# LCD_Disp_AIR.net
KiCad netlist of a schematic drawn in EAGLE
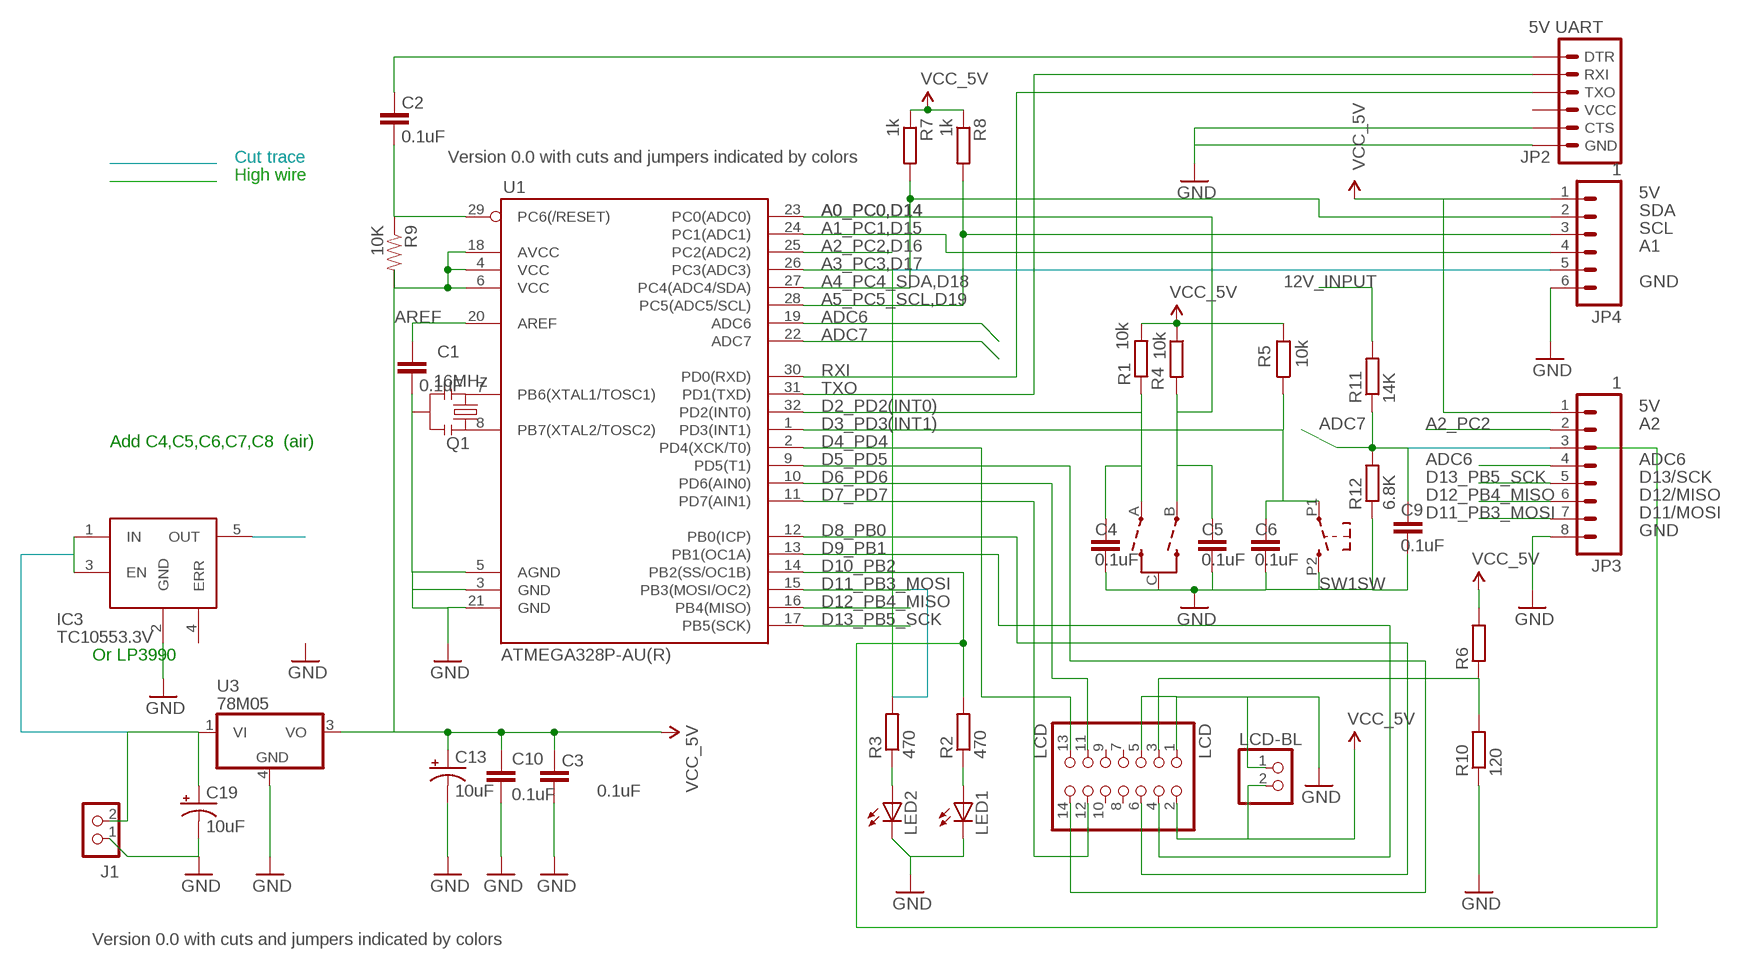
[diagram p0: schematic, sheet 1]

(export (version "E")
  (design (tool "Eeschema 10.0.6"))
  (components
    (comp (ref "C1")
      (value "0.1uF")
      (footprint "eagle-import:0805")
      (libsource (lib "eagle-import") (part "CAP0805"))
    )
    (comp (ref "C2")
      (value "0.1uF")
      (footprint "eagle-import:0805")
      (libsource (lib "eagle-import") (part "CAP0805"))
    )
    (comp (ref "C3")
      (value "0.1uF")
      (footprint "eagle-import:0805")
      (libsource (lib "eagle-import") (part "CAP0805"))
    )
    (comp (ref "C4")
      (value "0.1uF")
      (footprint "eagle-import:0805")
      (libsource (lib "eagle-import") (part "CAP0805"))
    )
    (comp (ref "C5")
      (value "0.1uF")
      (footprint "eagle-import:0805")
      (libsource (lib "eagle-import") (part "CAP0805"))
    )
    (comp (ref "C6")
      (value "0.1uF")
      (footprint "eagle-import:0805")
      (libsource (lib "eagle-import") (part "CAP0805"))
    )
    (comp (ref "C9")
      (value "0.1uF")
      (footprint "eagle-import:0805")
      (libsource (lib "eagle-import") (part "CAP0805"))
    )
    (comp (ref "C10")
      (value "0.1uF")
      (footprint "eagle-import:0805")
      (libsource (lib "eagle-import") (part "CAP0805"))
    )
    (comp (ref "C13")
      (value "10uF")
      (footprint "eagle-import:EIA3216")
      (libsource (lib "eagle-import") (part "CAP_POL1206"))
    )
    (comp (ref "C19")
      (value "10uF")
      (footprint "eagle-import:EIA7343")
      (libsource (lib "eagle-import") (part "CAP_POL7343"))
    )
    (comp (ref "IC3")
      (value "TC10553.3V")
      (footprint "eagle-import:SOT23-5")
      (libsource (lib "eagle-import") (part "TC10553.3V"))
    )
    (comp (ref "J1")
      (value "12V input")
      (footprint "eagle-import:M1X2")
      (libsource (lib "eagle-import") (part "CON_HEADER_1X02-PTH"))
    )
    (comp (ref "JP2")
      (value "5V UART")
      (footprint "eagle-import:1X06")
      (libsource (lib "eagle-import") (part "ARDUINO_SERIAL_PROGRAMPTH"))
    )
    (comp (ref "JP3")
      (value "1")
      (footprint "eagle-import:1X08")
      (libsource (lib "eagle-import") (part "M081X08"))
    )
    (comp (ref "JP4")
      (value "1")
      (footprint "eagle-import:1X06")
      (libsource (lib "eagle-import") (part "M06SIP"))
    )
    (comp (ref "LCD")
      (value "LCD")
      (footprint "eagle-import:2X07")
      (libsource (lib "eagle-import") (part "PINHD-2X7"))
    )
    (comp (ref "LCD-BL")
      (value "PINHD-1X2")
      (footprint "eagle-import:1X02")
      (libsource (lib "eagle-import") (part "PINHD-1X2"))
    )
    (comp (ref "LED1")
      (value "LED-5MM")
      (footprint "eagle-import:LED-5MM")
      (libsource (lib "eagle-import") (part "LED-5MM"))
    )
    (comp (ref "LED2")
      (value "LED-5MM")
      (footprint "eagle-import:LED-5MM")
      (libsource (lib "eagle-import") (part "LED-5MM"))
    )
    (comp (ref "Q1")
      (value "16MHz")
      (footprint "eagle-import:RESONATOR-SMD")
      (libsource (lib "eagle-import") (part "RESONATORSMD"))
    )
    (comp (ref "R1")
      (value "10k")
      (footprint "eagle-import:R603")
      (libsource (lib "eagle-import") (part "RESISTOR-0603"))
    )
    (comp (ref "R2")
      (value "470")
      (footprint "eagle-import:R603")
      (libsource (lib "eagle-import") (part "RESISTOR-0603"))
    )
    (comp (ref "R3")
      (value "470")
      (footprint "eagle-import:R603")
      (libsource (lib "eagle-import") (part "RESISTOR-0603"))
    )
    (comp (ref "R4")
      (value "10k")
      (footprint "eagle-import:R603")
      (libsource (lib "eagle-import") (part "RESISTOR-0603"))
    )
    (comp (ref "R5")
      (value "10k")
      (footprint "eagle-import:R603")
      (libsource (lib "eagle-import") (part "RESISTOR-0603"))
    )
    (comp (ref "R6")
      (value "RESISTOR-0603")
      (footprint "eagle-import:R603")
      (libsource (lib "eagle-import") (part "RESISTOR-0603"))
    )
    (comp (ref "R7")
      (value "1k")
      (footprint "eagle-import:R603")
      (libsource (lib "eagle-import") (part "RESISTOR-0603"))
    )
    (comp (ref "R8")
      (value "1k")
      (footprint "eagle-import:R603")
      (libsource (lib "eagle-import") (part "RESISTOR-0603"))
    )
    (comp (ref "R9")
      (value "10K")
      (footprint "eagle-import:0603")
      (libsource (lib "eagle-import") (part "RESISTOR0603"))
    )
    (comp (ref "R10")
      (value "120")
      (footprint "eagle-import:R603")
      (libsource (lib "eagle-import") (part "RESISTOR-0603"))
    )
    (comp (ref "R11")
      (value "14K")
      (footprint "eagle-import:R603")
      (libsource (lib "eagle-import") (part "RESISTOR-0603"))
    )
    (comp (ref "R12")
      (value "6.8K")
      (footprint "eagle-import:R603")
      (libsource (lib "eagle-import") (part "RESISTOR-0603"))
    )
    (comp (ref "SW1")
      (value "ENCODER_SW1-PEC12")
      (footprint "eagle-import:PEC12_INCREMENTAL_ENCODER")
      (libsource (lib "eagle-import") (part "ENCODER_SW1-PEC12"))
    )
    (comp (ref "U1")
      (value "ATMEGA328P-AU(R)")
      (footprint "eagle-import:TQFP32-08")
      (libsource (lib "eagle-import") (part "ATMEGA168"))
    )
    (comp (ref "U3")
      (value "78M05")
      (footprint "eagle-import:DPACK")
      (libsource (lib "eagle-import") (part "78MXXL"))
    )
  )
  (nets
    (net (code "1") (name "/12V_INPUT") (class "Default")
      (node (ref "C19") (pin "A") (pinfunction "+_A") (pintype "passive"))
      (node (ref "J1") (pin "2") (pinfunction "2_2") (pintype "passive"))
      (node (ref "R11") (pin "2") (pinfunction "2_2") (pintype "passive"))
      (node (ref "U3") (pin "1") (pinfunction "VI_1") (pintype "input"))
    )
    (net (code "2") (name "/A0_PC0,D14") (class "Default")
      (node (ref "C5") (pin "2") (pinfunction "2_2") (pintype "passive"))
      (node (ref "R4") (pin "2") (pinfunction "2_2") (pintype "passive"))
      (node (ref "SW1") (pin "B") (pinfunction "B_B") (pintype "passive"))
      (node (ref "U1") (pin "23") (pinfunction "PC0(ADC0)_23") (pintype "bidirectional"))
    )
    (net (code "3") (name "/A1_PC1,D15") (class "Default")
      (node (ref "JP4") (pin "4") (pinfunction "4_4") (pintype "passive"))
      (node (ref "U1") (pin "24") (pinfunction "PC1(ADC1)_24") (pintype "bidirectional"))
    )
    (net (code "4") (name "/A2_PC2") (class "Default")
      (node (ref "JP3") (pin "2") (pinfunction "2_2") (pintype "passive"))
    )
    (net (code "5") (name "/A2_PC2,D16") (class "Default")
      (node (ref "U1") (pin "25") (pinfunction "PC2(ADC2)_25") (pintype "bidirectional"))
    )
    (net (code "6") (name "/A3_PC3,D17") (class "Default")
      (node (ref "U1") (pin "26") (pinfunction "PC3(ADC3)_26") (pintype "bidirectional"))
    )
    (net (code "7") (name "/A4_PC4_SDA,D18") (class "Default")
      (node (ref "JP4") (pin "2") (pinfunction "2_2") (pintype "passive"))
      (node (ref "R7") (pin "2") (pinfunction "2_2") (pintype "passive"))
      (node (ref "U1") (pin "27") (pinfunction "PC4(ADC4/SDA)_27") (pintype "bidirectional"))
    )
    (net (code "8") (name "/A5_PC5_SCL,D19") (class "Default")
      (node (ref "JP4") (pin "3") (pinfunction "3_3") (pintype "passive"))
      (node (ref "R8") (pin "2") (pinfunction "2_2") (pintype "passive"))
      (node (ref "U1") (pin "28") (pinfunction "PC5(ADC5/SCL)_28") (pintype "bidirectional"))
    )
    (net (code "9") (name "/ADC6") (class "Default")
      (node (ref "JP3") (pin "4") (pinfunction "4_4") (pintype "passive"))
      (node (ref "U1") (pin "19") (pinfunction "ADC6_19") (pintype "bidirectional"))
    )
    (net (code "10") (name "/ADC7") (class "Default")
      (node (ref "C9") (pin "1") (pinfunction "1_1") (pintype "passive"))
      (node (ref "R11") (pin "1") (pinfunction "1_1") (pintype "passive"))
      (node (ref "R12") (pin "2") (pinfunction "2_2") (pintype "passive"))
      (node (ref "U1") (pin "22") (pinfunction "ADC7_22") (pintype "bidirectional"))
    )
    (net (code "11") (name "/AREF") (class "Default")
      (node (ref "C1") (pin "2") (pinfunction "2_2") (pintype "passive"))
      (node (ref "U1") (pin "20") (pinfunction "AREF_20") (pintype "bidirectional"))
    )
    (net (code "12") (name "/D2_PD2(INT0)") (class "Default")
      (node (ref "C4") (pin "2") (pinfunction "2_2") (pintype "passive"))
      (node (ref "R1") (pin "1") (pinfunction "1_1") (pintype "passive"))
      (node (ref "SW1") (pin "A") (pinfunction "A_A") (pintype "passive"))
      (node (ref "U1") (pin "32") (pinfunction "PD2(INT0)_32") (pintype "bidirectional"))
    )
    (net (code "13") (name "/D3_PD3(INT1)") (class "Default")
      (node (ref "C6") (pin "2") (pinfunction "2_2") (pintype "passive"))
      (node (ref "R5") (pin "1") (pinfunction "1_1") (pintype "passive"))
      (node (ref "SW1") (pin "P1") (pinfunction "1_P1") (pintype "passive"))
      (node (ref "U1") (pin "1") (pinfunction "PD3(INT1)_1") (pintype "bidirectional"))
    )
    (net (code "14") (name "/D4_PD4") (class "Default")
      (node (ref "LCD") (pin "13") (pinfunction "13_13") (pintype "passive"))
      (node (ref "U1") (pin "2") (pinfunction "PD4(XCK/T0)_2") (pintype "bidirectional"))
    )
    (net (code "15") (name "/D5_PD5") (class "Default")
      (node (ref "LCD") (pin "14") (pinfunction "14_14") (pintype "passive"))
      (node (ref "U1") (pin "9") (pinfunction "PD5(T1)_9") (pintype "bidirectional"))
    )
    (net (code "16") (name "/D6_PD6") (class "Default")
      (node (ref "LCD") (pin "11") (pinfunction "11_11") (pintype "passive"))
      (node (ref "U1") (pin "10") (pinfunction "PD6(AIN0)_10") (pintype "bidirectional"))
    )
    (net (code "17") (name "/D7_PD7") (class "Default")
      (node (ref "LCD") (pin "12") (pinfunction "12_12") (pintype "passive"))
      (node (ref "U1") (pin "11") (pinfunction "PD7(AIN1)_11") (pintype "bidirectional"))
    )
    (net (code "18") (name "/D8_PB0") (class "Default")
      (node (ref "LCD") (pin "6") (pinfunction "6_6") (pintype "passive"))
      (node (ref "U1") (pin "12") (pinfunction "PB0(ICP)_12") (pintype "bidirectional"))
    )
    (net (code "19") (name "/D9_PB1") (class "Default")
      (node (ref "LCD") (pin "4") (pinfunction "4_4") (pintype "passive"))
      (node (ref "U1") (pin "13") (pinfunction "PB1(OC1A)_13") (pintype "bidirectional"))
    )
    (net (code "20") (name "/D10_PB2") (class "Default")
      (node (ref "R2") (pin "2") (pinfunction "2_2") (pintype "passive"))
      (node (ref "U1") (pin "14") (pinfunction "PB2(SS/OC1B)_14") (pintype "bidirectional"))
    )
    (net (code "21") (name "/D11_PB3_MOSI") (class "Default")
      (node (ref "JP3") (pin "7") (pinfunction "7_7") (pintype "passive"))
      (node (ref "U1") (pin "15") (pinfunction "PB3(MOSI/OC2)_15") (pintype "bidirectional"))
    )
    (net (code "22") (name "/D12_PB4_MISO") (class "Default")
      (node (ref "JP3") (pin "6") (pinfunction "6_6") (pintype "passive"))
      (node (ref "U1") (pin "16") (pinfunction "PB4(MISO)_16") (pintype "bidirectional"))
    )
    (net (code "23") (name "/D13_PB5_SCK") (class "Default")
      (node (ref "JP3") (pin "5") (pinfunction "5_5") (pintype "passive"))
      (node (ref "U1") (pin "17") (pinfunction "PB5(SCK)_17") (pintype "bidirectional"))
    )
    (net (code "24") (name "/OUT") (class "Default")
      (node (ref "IC3") (pin "5") (pinfunction "OUT_5") (pintype "power_in"))
    )
    (net (code "25") (name "/RXI") (class "Default")
      (node (ref "JP2") (pin "3") (pinfunction "TXO_3") (pintype "passive"))
      (node (ref "U1") (pin "30") (pinfunction "PD0(RXD)_30") (pintype "bidirectional"))
    )
    (net (code "26") (name "/TXO") (class "Default")
      (node (ref "JP2") (pin "2") (pinfunction "RXI_2") (pintype "passive"))
      (node (ref "U1") (pin "31") (pinfunction "PD1(TXD)_31") (pintype "bidirectional"))
    )
    (net (code "27") (name "GND") (class "Default")
      (node (ref "C1") (pin "1") (pinfunction "1_1") (pintype "passive"))
      (node (ref "C10") (pin "2") (pinfunction "2_2") (pintype "passive"))
      (node (ref "C13") (pin "C") (pinfunction "-_C") (pintype "passive"))
      (node (ref "C19") (pin "C") (pinfunction "-_C") (pintype "passive"))
      (node (ref "C3") (pin "1") (pinfunction "1_1") (pintype "passive"))
      (node (ref "C4") (pin "1") (pinfunction "1_1") (pintype "passive"))
      (node (ref "C5") (pin "1") (pinfunction "1_1") (pintype "passive"))
      (node (ref "C6") (pin "1") (pinfunction "1_1") (pintype "passive"))
      (node (ref "C9") (pin "2") (pinfunction "2_2") (pintype "passive"))
      (node (ref "IC3") (pin "2") (pinfunction "GND_2") (pintype "power_in"))
      (node (ref "J1") (pin "1") (pinfunction "1_1") (pintype "passive"))
      (node (ref "JP2") (pin "5") (pinfunction "CTS_5") (pintype "passive"))
      (node (ref "JP2") (pin "6") (pinfunction "GND_6") (pintype "passive"))
      (node (ref "JP3") (pin "8") (pinfunction "8_8") (pintype "passive"))
      (node (ref "JP4") (pin "6") (pinfunction "6_6") (pintype "passive"))
      (node (ref "LCD") (pin "1") (pinfunction "1_1") (pintype "passive"))
      (node (ref "LCD") (pin "5") (pinfunction "5_5") (pintype "passive"))
      (node (ref "LCD-BL") (pin "1") (pinfunction "1_1") (pintype "passive"))
      (node (ref "LED1") (pin "K") (pinfunction "C_K") (pintype "passive"))
      (node (ref "LED2") (pin "K") (pinfunction "C_K") (pintype "passive"))
      (node (ref "Q1") (pin "2") (pinfunction "2_2") (pintype "passive"))
      (node (ref "R10") (pin "1") (pinfunction "1_1") (pintype "passive"))
      (node (ref "R12") (pin "1") (pinfunction "1_1") (pintype "passive"))
      (node (ref "SW1") (pin "C") (pinfunction "C_C") (pintype "passive"))
      (node (ref "SW1") (pin "P2") (pinfunction "2_P2") (pintype "passive"))
      (node (ref "U1") (pin "21") (pinfunction "GND_21") (pintype "bidirectional"))
      (node (ref "U1") (pin "3") (pinfunction "GND_3") (pintype "bidirectional"))
      (node (ref "U1") (pin "5") (pinfunction "AGND_5") (pintype "bidirectional"))
      (node (ref "U3") (pin "4") (pinfunction "GND_4") (pintype "passive"))
    )
    (net (code "28") (name "Net-(IC3-EN)") (class "Default")
      (node (ref "IC3") (pin "1") (pinfunction "IN_1") (pintype "power_in"))
      (node (ref "IC3") (pin "3") (pinfunction "EN_3") (pintype "input"))
    )
    (net (code "29") (name "Net-(JP2-DTR)") (class "Default")
      (node (ref "C2") (pin "2") (pinfunction "2_2") (pintype "passive"))
      (node (ref "JP2") (pin "1") (pinfunction "DTR_1") (pintype "passive"))
    )
    (net (code "30") (name "Net-(LCD-Pad3)") (class "Default")
      (node (ref "LCD") (pin "3") (pinfunction "3_3") (pintype "passive"))
      (node (ref "R10") (pin "2") (pinfunction "2_2") (pintype "passive"))
      (node (ref "R6") (pin "1") (pinfunction "1_1") (pintype "passive"))
    )
    (net (code "31") (name "Net-(LED1-PadA)") (class "Default")
      (node (ref "LED1") (pin "A") (pinfunction "A_A") (pintype "passive"))
      (node (ref "R2") (pin "1") (pinfunction "1_1") (pintype "passive"))
    )
    (net (code "32") (name "Net-(LED2-PadA)") (class "Default")
      (node (ref "LED2") (pin "A") (pinfunction "A_A") (pintype "passive"))
      (node (ref "R3") (pin "1") (pinfunction "1_1") (pintype "passive"))
    )
    (net (code "33") (name "Net-(U1-PB6(XTAL1{slash}TOSC1))") (class "Default")
      (node (ref "Q1") (pin "3") (pinfunction "3_3") (pintype "passive"))
      (node (ref "U1") (pin "7") (pinfunction "PB6(XTAL1/TOSC1)_7") (pintype "bidirectional"))
    )
    (net (code "34") (name "Net-(U1-PB7(XTAL2{slash}TOSC2))") (class "Default")
      (node (ref "Q1") (pin "1") (pinfunction "1_1") (pintype "passive"))
      (node (ref "U1") (pin "8") (pinfunction "PB7(XTAL2/TOSC2)_8") (pintype "bidirectional"))
    )
    (net (code "35") (name "Net-(U1-PC6({slash}RESET))") (class "Default")
      (node (ref "C2") (pin "1") (pinfunction "1_1") (pintype "passive"))
      (node (ref "R9") (pin "1") (pinfunction "1_1") (pintype "passive"))
      (node (ref "U1") (pin "29") (pinfunction "PC6(/RESET)_29") (pintype "bidirectional"))
    )
    (net (code "36") (name "VCC_5V") (class "Default")
      (node (ref "C10") (pin "1") (pinfunction "1_1") (pintype "passive"))
      (node (ref "C13") (pin "A") (pinfunction "+_A") (pintype "passive"))
      (node (ref "C3") (pin "2") (pinfunction "2_2") (pintype "passive"))
      (node (ref "JP3") (pin "1") (pinfunction "1_1") (pintype "passive"))
      (node (ref "JP4") (pin "1") (pinfunction "1_1") (pintype "passive"))
      (node (ref "LCD") (pin "2") (pinfunction "2_2") (pintype "passive"))
      (node (ref "LCD-BL") (pin "2") (pinfunction "2_2") (pintype "passive"))
      (node (ref "R1") (pin "2") (pinfunction "2_2") (pintype "passive"))
      (node (ref "R4") (pin "1") (pinfunction "1_1") (pintype "passive"))
      (node (ref "R5") (pin "2") (pinfunction "2_2") (pintype "passive"))
      (node (ref "R6") (pin "2") (pinfunction "2_2") (pintype "passive"))
      (node (ref "R7") (pin "1") (pinfunction "1_1") (pintype "passive"))
      (node (ref "R8") (pin "1") (pinfunction "1_1") (pintype "passive"))
      (node (ref "R9") (pin "2") (pinfunction "2_2") (pintype "passive"))
      (node (ref "U1") (pin "18") (pinfunction "AVCC_18") (pintype "bidirectional"))
      (node (ref "U1") (pin "4") (pinfunction "VCC_4") (pintype "bidirectional"))
      (node (ref "U1") (pin "6") (pinfunction "VCC_6") (pintype "bidirectional"))
      (node (ref "U3") (pin "3") (pinfunction "VO_3") (pintype "passive"))
    )
    (net (code "37") (name "unconnected-(IC3-ERR-Pad4)") (class "Default")
      (node (ref "IC3") (pin "4") (pinfunction "ERR_4") (pintype "output"))
    )
    (net (code "38") (name "unconnected-(JP2-VCC-Pad4)") (class "Default")
      (node (ref "JP2") (pin "4") (pinfunction "VCC_4") (pintype "passive"))
    )
    (net (code "39") (name "unconnected-(JP3-Pad3)") (class "Default")
      (node (ref "JP3") (pin "3") (pinfunction "3_3") (pintype "passive"))
    )
    (net (code "40") (name "unconnected-(JP4-Pad5)") (class "Default")
      (node (ref "JP4") (pin "5") (pinfunction "5_5") (pintype "passive"))
    )
    (net (code "41") (name "unconnected-(LCD-Pad7)") (class "Default")
      (node (ref "LCD") (pin "7") (pinfunction "7_7") (pintype "passive"))
    )
    (net (code "42") (name "unconnected-(LCD-Pad8)") (class "Default")
      (node (ref "LCD") (pin "8") (pinfunction "8_8") (pintype "passive"))
    )
    (net (code "43") (name "unconnected-(LCD-Pad9)") (class "Default")
      (node (ref "LCD") (pin "9") (pinfunction "9_9") (pintype "passive"))
    )
    (net (code "44") (name "unconnected-(LCD-Pad10)") (class "Default")
      (node (ref "LCD") (pin "10") (pinfunction "10_10") (pintype "passive"))
    )
    (net (code "45") (name "unconnected-(R3-Pad2)") (class "Default")
      (node (ref "R3") (pin "2") (pinfunction "2_2") (pintype "passive"))
    )
  )
)
